# Main.net
KiCad netlist of a schematic drawn in Altium Designer
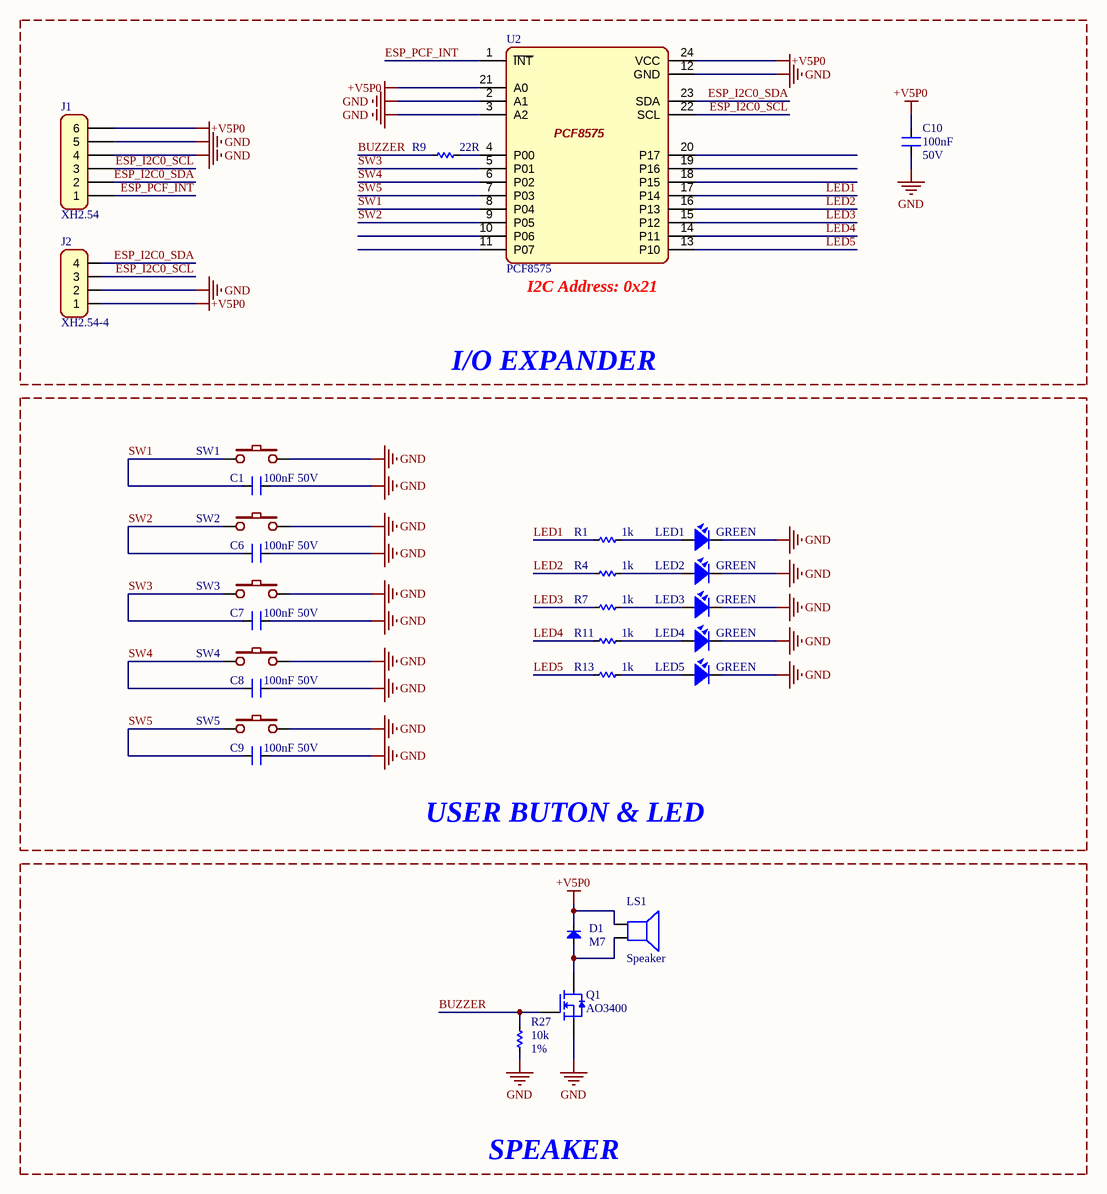
[diagram p0: Main.SchDoc]

(export (version "E")
  (design (tool "Eeschema 10.0.6"))
  (components
    (comp (ref "C1")
      (value "100nF")
      (footprint "Library_HUNG:CAP_SMD_0805")
      (fields (field (name "RATING") "50V"))
      (libsource (lib "Library_HUNG") (part "CN"))
    )
    (comp (ref "C6")
      (value "100nF")
      (footprint "Library_HUNG:CAP_SMD_0805")
      (fields (field (name "RATING") "50V"))
      (libsource (lib "Library_HUNG") (part "CN"))
    )
    (comp (ref "C7")
      (value "100nF")
      (footprint "Library_HUNG:CAP_SMD_0805")
      (fields (field (name "RATING") "50V"))
      (libsource (lib "Library_HUNG") (part "CN"))
    )
    (comp (ref "C8")
      (value "100nF")
      (footprint "Library_HUNG:CAP_SMD_0805")
      (fields (field (name "RATING") "50V"))
      (libsource (lib "Library_HUNG") (part "CN"))
    )
    (comp (ref "C9")
      (value "100nF")
      (footprint "Library_HUNG:CAP_SMD_0805")
      (fields (field (name "RATING") "50V"))
      (libsource (lib "Library_HUNG") (part "CN"))
    )
    (comp (ref "C10")
      (value "100nF")
      (footprint "Library_HUNG:CAP_SMD_0805")
      (fields (field (name "RATING") "50V"))
      (libsource (lib "Library_HUNG") (part "CN"))
    )
    (comp (ref "D1")
      (value "M7")
      (footprint "DIO-SMD-A")
      (description "Default Diode")
      (libsource (lib "Library_HUNG") (part "Diode SMD"))
    )
    (comp (ref "J1")
      (value "XH2.54")
      (footprint "XH2.54-6P-TH")
      (libsource (lib "Library_HUNG") (part "Header6"))
    )
    (comp (ref "J2")
      (value "XH2.54-4")
      (footprint "Header4")
      (description "Header IDC, 4 x 1 Pin Vertical 2.54mm Pitch (Non-Boxed, Male)")
      (libsource (lib "Library_HUNG") (part "Header4"))
    )
    (comp (ref "LED1")
      (value "GREEN")
      (footprint "LED-3MM-GREEN")
      (libsource (lib "Library_HUNG") (part "LED SMD"))
    )
    (comp (ref "LED2")
      (value "GREEN")
      (footprint "LED-3MM-GREEN")
      (libsource (lib "Library_HUNG") (part "LED SMD"))
    )
    (comp (ref "LED3")
      (value "GREEN")
      (footprint "LED-3MM-GREEN")
      (libsource (lib "Library_HUNG") (part "LED SMD"))
    )
    (comp (ref "LED4")
      (value "GREEN")
      (footprint "LED-3MM-GREEN")
      (libsource (lib "Library_HUNG") (part "LED SMD"))
    )
    (comp (ref "LED5")
      (value "GREEN")
      (footprint "LED-3MM-GREEN")
      (libsource (lib "Library_HUNG") (part "LED SMD"))
    )
    (comp (ref "LS1")
      (value "Speaker")
      (footprint "SPEAKER")
      (description "Loudspeaker")
      (fields (field (name "PUBLISHER") "Altium Limited"))
      (libsource (lib "Library_HUNG") (part "Speaker"))
    )
    (comp (ref "Q1") (value "AO3400") (footprint "SOT23-123") (libsource (lib "Library_HUNG") (part "FET-N")))
    (comp (ref "R1")
      (value "1k")
      (footprint "Library_HUNG:RES_SMD_0805")
      (description "Resistor")
      (fields (field (name "TOLERANCE") "1%"))
      (libsource (lib "Library_HUNG") (part "Res-SMD"))
    )
    (comp (ref "R4")
      (value "1k")
      (footprint "Library_HUNG:RES_SMD_0805")
      (description "Resistor")
      (fields (field (name "TOLERANCE") "1%"))
      (libsource (lib "Library_HUNG") (part "Res-SMD"))
    )
    (comp (ref "R7")
      (value "1k")
      (footprint "Library_HUNG:RES_SMD_0805")
      (description "Resistor")
      (fields (field (name "TOLERANCE") "1%"))
      (libsource (lib "Library_HUNG") (part "Res-SMD"))
    )
    (comp (ref "R9")
      (value "22R")
      (footprint "Library_HUNG:RES_SMD_0805")
      (description "Resistor")
      (fields (field (name "TOLERANCE") "1%"))
      (libsource (lib "Library_HUNG") (part "Res-SMD"))
    )
    (comp (ref "R11")
      (value "1k")
      (footprint "Library_HUNG:RES_SMD_0805")
      (description "Resistor")
      (fields (field (name "TOLERANCE") "1%"))
      (libsource (lib "Library_HUNG") (part "Res-SMD"))
    )
    (comp (ref "R13")
      (value "1k")
      (footprint "Library_HUNG:RES_SMD_0805")
      (description "Resistor")
      (fields (field (name "TOLERANCE") "1%"))
      (libsource (lib "Library_HUNG") (part "Res-SMD"))
    )
    (comp (ref "R27")
      (value "10k")
      (footprint "Library_HUNG:RES_SMD_0805")
      (description "Resistor")
      (fields (field (name "TOLERANCE") "1%"))
      (libsource (lib "Library_HUNG") (part "Res-SMD"))
    )
    (comp (ref "SW1")
      (value "SW2")
      (footprint "SW-6X6MM")
      (description "Switch button 2 pin")
      (libsource (lib "Library_HUNG") (part "SW2"))
    )
    (comp (ref "SW2")
      (value "SW2")
      (footprint "SW-6X6MM")
      (description "Switch button 2 pin")
      (libsource (lib "Library_HUNG") (part "SW2"))
    )
    (comp (ref "SW3")
      (value "SW2")
      (footprint "SW-6X6MM")
      (description "Switch button 2 pin")
      (libsource (lib "Library_HUNG") (part "SW2"))
    )
    (comp (ref "SW4")
      (value "SW2")
      (footprint "SW-6X6MM")
      (description "Switch button 2 pin")
      (libsource (lib "Library_HUNG") (part "SW2"))
    )
    (comp (ref "SW5")
      (value "SW2")
      (footprint "SW-6X6MM")
      (description "Switch button 2 pin")
      (libsource (lib "Library_HUNG") (part "SW2"))
    )
    (comp (ref "U2")
      (value "PCF8575")
      (footprint "SSOP-24-208mil")
      (libsource (lib "Library_HUNG") (part "PCF8575"))
    )
  )
  (nets
    (net (code "1") (name "+V5P0") (class "Default")
      (node (ref "C10") (pin "1") (pinfunction "1_1") (pintype "passive"))
      (node (ref "D1") (pin "2") (pinfunction "K_2") (pintype "passive"))
      (node (ref "J1") (pin "6") (pinfunction "6_6") (pintype "passive"))
      (node (ref "J2") (pin "1") (pinfunction "1_1") (pintype "passive"))
      (node (ref "LS1") (pin "1") (pinfunction "1_1") (pintype "passive"))
      (node (ref "U2") (pin "21") (pinfunction "A0_21") (pintype "passive"))
      (node (ref "U2") (pin "24") (pinfunction "VCC_24") (pintype "passive"))
    )
    (net (code "2") (name "/BUZZER") (class "Default")
      (node (ref "Q1") (pin "1") (pintype "passive"))
      (node (ref "R27") (pin "1") (pinfunction "1_1") (pintype "passive"))
      (node (ref "R9") (pin "2") (pinfunction "2_2") (pintype "passive"))
    )
    (net (code "3") (name "/ESP_I2C0_SCL") (class "Default")
      (node (ref "J1") (pin "3") (pinfunction "3_3") (pintype "passive"))
      (node (ref "J2") (pin "3") (pinfunction "3_3") (pintype "passive"))
      (node (ref "U2") (pin "22") (pinfunction "SCL_22") (pintype "passive"))
    )
    (net (code "4") (name "/ESP_I2C0_SDA") (class "Default")
      (node (ref "J1") (pin "2") (pinfunction "2_2") (pintype "passive"))
      (node (ref "J2") (pin "4") (pinfunction "4_4") (pintype "passive"))
      (node (ref "U2") (pin "23") (pinfunction "SDA_23") (pintype "passive"))
    )
    (net (code "5") (name "/ESP_PCF_INT") (class "Default")
      (node (ref "J1") (pin "1") (pinfunction "1_1") (pintype "passive"))
      (node (ref "U2") (pin "1") (pinfunction "~{INT}_1") (pintype "passive"))
    )
    (net (code "6") (name "/LED1") (class "Default")
      (node (ref "R1") (pin "2") (pinfunction "2_2") (pintype "passive"))
      (node (ref "U2") (pin "17") (pinfunction "P14_17") (pintype "passive"))
    )
    (net (code "7") (name "/LED2") (class "Default")
      (node (ref "R4") (pin "2") (pinfunction "2_2") (pintype "passive"))
      (node (ref "U2") (pin "16") (pinfunction "P13_16") (pintype "passive"))
    )
    (net (code "8") (name "/LED3") (class "Default")
      (node (ref "R7") (pin "2") (pinfunction "2_2") (pintype "passive"))
      (node (ref "U2") (pin "15") (pinfunction "P12_15") (pintype "passive"))
    )
    (net (code "9") (name "/LED4") (class "Default")
      (node (ref "R11") (pin "2") (pinfunction "2_2") (pintype "passive"))
      (node (ref "U2") (pin "14") (pinfunction "P11_14") (pintype "passive"))
    )
    (net (code "10") (name "/LED5") (class "Default")
      (node (ref "R13") (pin "2") (pinfunction "2_2") (pintype "passive"))
      (node (ref "U2") (pin "13") (pinfunction "P10_13") (pintype "passive"))
    )
    (net (code "11") (name "/SW1") (class "Default")
      (node (ref "C1") (pin "1") (pinfunction "1_1") (pintype "passive"))
      (node (ref "SW1") (pin "1") (pinfunction "1_1") (pintype "passive"))
      (node (ref "U2") (pin "8") (pinfunction "P04_8") (pintype "passive"))
    )
    (net (code "12") (name "/SW2") (class "Default")
      (node (ref "C6") (pin "1") (pinfunction "1_1") (pintype "passive"))
      (node (ref "SW2") (pin "1") (pinfunction "1_1") (pintype "passive"))
      (node (ref "U2") (pin "9") (pinfunction "P05_9") (pintype "passive"))
    )
    (net (code "13") (name "/SW3") (class "Default")
      (node (ref "C7") (pin "1") (pinfunction "1_1") (pintype "passive"))
      (node (ref "SW3") (pin "1") (pinfunction "1_1") (pintype "passive"))
      (node (ref "U2") (pin "5") (pinfunction "P01_5") (pintype "passive"))
    )
    (net (code "14") (name "/SW4") (class "Default")
      (node (ref "C8") (pin "1") (pinfunction "1_1") (pintype "passive"))
      (node (ref "SW4") (pin "1") (pinfunction "1_1") (pintype "passive"))
      (node (ref "U2") (pin "6") (pinfunction "P02_6") (pintype "passive"))
    )
    (net (code "15") (name "/SW5") (class "Default")
      (node (ref "C9") (pin "1") (pinfunction "1_1") (pintype "passive"))
      (node (ref "SW5") (pin "1") (pinfunction "1_1") (pintype "passive"))
      (node (ref "U2") (pin "7") (pinfunction "P03_7") (pintype "passive"))
    )
    (net (code "16") (name "GND") (class "Default")
      (node (ref "C1") (pin "2") (pinfunction "2_2") (pintype "passive"))
      (node (ref "C10") (pin "2") (pinfunction "2_2") (pintype "passive"))
      (node (ref "C6") (pin "2") (pinfunction "2_2") (pintype "passive"))
      (node (ref "C7") (pin "2") (pinfunction "2_2") (pintype "passive"))
      (node (ref "C8") (pin "2") (pinfunction "2_2") (pintype "passive"))
      (node (ref "C9") (pin "2") (pinfunction "2_2") (pintype "passive"))
      (node (ref "J1") (pin "4") (pinfunction "4_4") (pintype "passive"))
      (node (ref "J1") (pin "5") (pinfunction "5_5") (pintype "passive"))
      (node (ref "J2") (pin "2") (pinfunction "2_2") (pintype "passive"))
      (node (ref "LED1") (pin "2") (pinfunction "2_2") (pintype "passive"))
      (node (ref "LED2") (pin "2") (pinfunction "2_2") (pintype "passive"))
      (node (ref "LED3") (pin "2") (pinfunction "2_2") (pintype "passive"))
      (node (ref "LED4") (pin "2") (pinfunction "2_2") (pintype "passive"))
      (node (ref "LED5") (pin "2") (pinfunction "2_2") (pintype "passive"))
      (node (ref "Q1") (pin "2") (pintype "power_in"))
      (node (ref "R27") (pin "2") (pinfunction "2_2") (pintype "passive"))
      (node (ref "SW1") (pin "2") (pinfunction "2_2") (pintype "passive"))
      (node (ref "SW2") (pin "2") (pinfunction "2_2") (pintype "passive"))
      (node (ref "SW3") (pin "2") (pinfunction "2_2") (pintype "passive"))
      (node (ref "SW4") (pin "2") (pinfunction "2_2") (pintype "passive"))
      (node (ref "SW5") (pin "2") (pinfunction "2_2") (pintype "passive"))
      (node (ref "U2") (pin "12") (pinfunction "GND_12") (pintype "passive"))
      (node (ref "U2") (pin "2") (pinfunction "A1_2") (pintype "passive"))
      (node (ref "U2") (pin "3") (pinfunction "A2_3") (pintype "passive"))
    )
    (net (code "17") (name "Net-(D1-A)") (class "Default")
      (node (ref "D1") (pin "1") (pinfunction "A_1") (pintype "passive"))
      (node (ref "LS1") (pin "2") (pinfunction "2_2") (pintype "passive"))
      (node (ref "Q1") (pin "3") (pintype "power_in"))
    )
    (net (code "18") (name "Net-(LED1-Pad1)") (class "Default")
      (node (ref "LED1") (pin "1") (pinfunction "1_1") (pintype "passive"))
      (node (ref "R1") (pin "1") (pinfunction "1_1") (pintype "passive"))
    )
    (net (code "19") (name "Net-(LED2-Pad1)") (class "Default")
      (node (ref "LED2") (pin "1") (pinfunction "1_1") (pintype "passive"))
      (node (ref "R4") (pin "1") (pinfunction "1_1") (pintype "passive"))
    )
    (net (code "20") (name "Net-(LED3-Pad1)") (class "Default")
      (node (ref "LED3") (pin "1") (pinfunction "1_1") (pintype "passive"))
      (node (ref "R7") (pin "1") (pinfunction "1_1") (pintype "passive"))
    )
    (net (code "21") (name "Net-(LED4-Pad1)") (class "Default")
      (node (ref "LED4") (pin "1") (pinfunction "1_1") (pintype "passive"))
      (node (ref "R11") (pin "1") (pinfunction "1_1") (pintype "passive"))
    )
    (net (code "22") (name "Net-(LED5-Pad1)") (class "Default")
      (node (ref "LED5") (pin "1") (pinfunction "1_1") (pintype "passive"))
      (node (ref "R13") (pin "1") (pinfunction "1_1") (pintype "passive"))
    )
    (net (code "23") (name "Net-(U2-P00)") (class "Default")
      (node (ref "R9") (pin "1") (pinfunction "1_1") (pintype "passive"))
      (node (ref "U2") (pin "4") (pinfunction "P00_4") (pintype "passive"))
    )
    (net (code "24") (name "unconnected-(U2-P06-Pad10)") (class "Default")
      (node (ref "U2") (pin "10") (pinfunction "P06_10") (pintype "passive"))
    )
    (net (code "25") (name "unconnected-(U2-P07-Pad11)") (class "Default")
      (node (ref "U2") (pin "11") (pinfunction "P07_11") (pintype "passive"))
    )
    (net (code "26") (name "unconnected-(U2-P15-Pad18)") (class "Default")
      (node (ref "U2") (pin "18") (pinfunction "P15_18") (pintype "passive"))
    )
    (net (code "27") (name "unconnected-(U2-P16-Pad19)") (class "Default")
      (node (ref "U2") (pin "19") (pinfunction "P16_19") (pintype "passive"))
    )
    (net (code "28") (name "unconnected-(U2-P17-Pad20)") (class "Default")
      (node (ref "U2") (pin "20") (pinfunction "P17_20") (pintype "passive"))
    )
  )
)
